# design.net
KiCad netlist of a schematic drawn in EasyEDA Pro
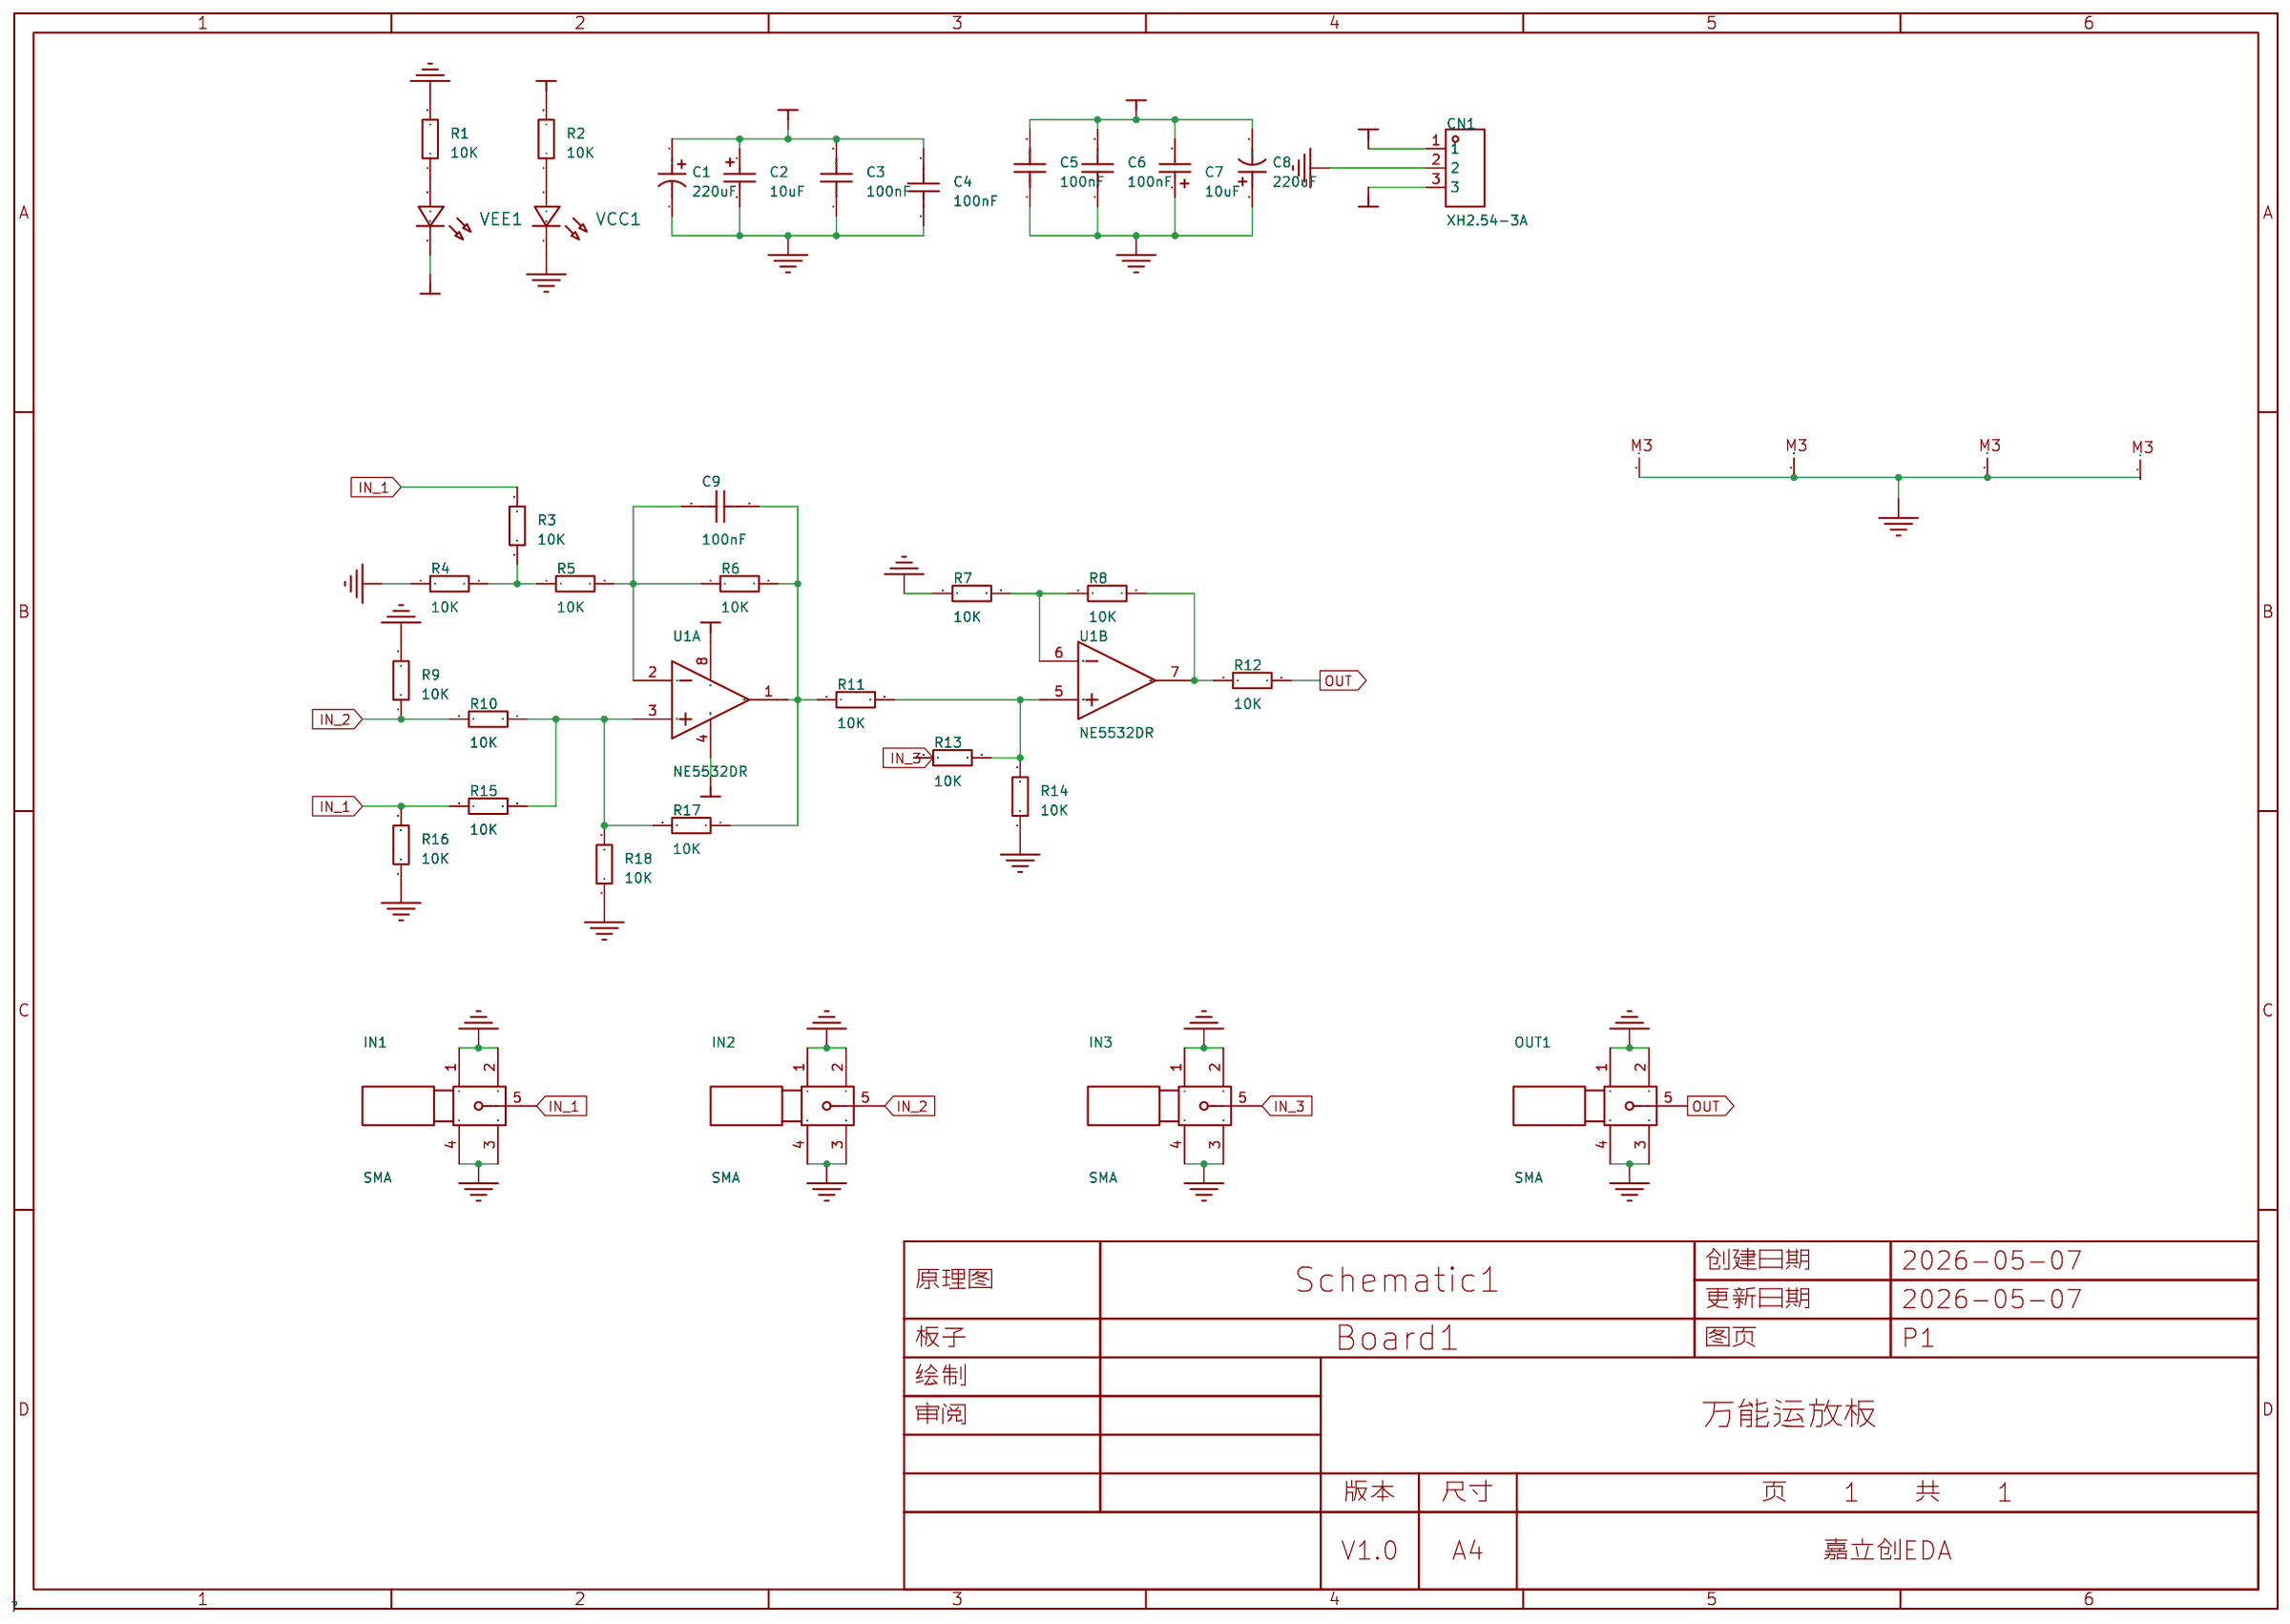
[diagram p0: schematic sheet]

(export (version "E")
  (design (tool "Eeschema 10.0.6"))
  (components
    (comp (ref "C1")
      (value "220uF")
      (footprint "easyedapro:CAP-SMD_BD6.3-L6.6-W6.6-LS7.3-FD-H7.7")
      (fields (field (name "Manufacturer Part") "JVJ25V220M6x8") (field (name "Manufacturer") "JIERR(捷而瑞)"))
      (libsource (lib "easyedapro") (part "JVJ25V220M6X8"))
    )
    (comp (ref "C2")
      (value "10uF")
      (footprint "easyedapro:CAP-SMD_L3.2-W1.6-RD-C7171")
      (fields (field (name "Manufacturer Part") "TAJA106K016RNJ") (field (name "Manufacturer") "Kyocera AVX"))
      (libsource (lib "easyedapro") (part "TAJA106K016RNJ"))
    )
    (comp (ref "C3")
      (value "100nF")
      (footprint "easyedapro:C0603")
      (libsource (lib "easyedapro") (part "Capacitance"))
    )
    (comp (ref "C4")
      (value "100nF")
      (footprint "easyedapro:C0603")
      (libsource (lib "easyedapro") (part "Capacitance"))
    )
    (comp (ref "C5")
      (value "100nF")
      (footprint "easyedapro:C0603")
      (libsource (lib "easyedapro") (part "Capacitance"))
    )
    (comp (ref "C6")
      (value "100nF")
      (footprint "easyedapro:C0603")
      (libsource (lib "easyedapro") (part "Capacitance"))
    )
    (comp (ref "C7")
      (value "10uF")
      (footprint "easyedapro:CAP-SMD_L3.2-W1.6-RD-C7171")
      (fields (field (name "Manufacturer Part") "TAJA106K016RNJ") (field (name "Manufacturer") "Kyocera AVX"))
      (libsource (lib "easyedapro") (part "TAJA106K016RNJ"))
    )
    (comp (ref "C8")
      (value "220uF")
      (footprint "easyedapro:CAP-SMD_BD6.3-L6.6-W6.6-LS7.3-FD-H7.7")
      (fields (field (name "Manufacturer Part") "JVJ25V220M6x8") (field (name "Manufacturer") "JIERR(捷而瑞)"))
      (libsource (lib "easyedapro") (part "JVJ25V220M6X8"))
    )
    (comp (ref "C9")
      (value "100nF")
      (footprint "easyedapro:C0603")
      (libsource (lib "easyedapro") (part "Capacitance"))
    )
    (comp (ref "CN1")
      (value "XH2.54-3A")
      (footprint "easyedapro:CONN-TH_3P-P2.50_HCTL_XH-3A-L")
      (libsource (lib "easyedapro") (part "XH2.54-3A"))
    )
    (comp (ref "IN1")
      (value "SMA")
      (footprint "easyedapro:SMA-SMD_BWSMA-KE-P001")
      (libsource (lib "easyedapro") (part "SMA_C9900018296"))
    )
    (comp (ref "IN2")
      (value "SMA")
      (footprint "easyedapro:SMA-SMD_BWSMA-KE-P001")
      (libsource (lib "easyedapro") (part "SMA_C9900018296"))
    )
    (comp (ref "IN3")
      (value "SMA")
      (footprint "easyedapro:SMA-SMD_BWSMA-KE-P001")
      (libsource (lib "easyedapro") (part "SMA_C9900018296"))
    )
    (comp (ref "M1") (value "~") (footprint "easyedapro:M3") (libsource (lib "easyedapro") (part "螺丝孔")))
    (comp (ref "M2") (value "~") (footprint "easyedapro:M3") (libsource (lib "easyedapro") (part "螺丝孔")))
    (comp (ref "M3") (value "~") (footprint "easyedapro:M3") (libsource (lib "easyedapro") (part "螺丝孔")))
    (comp (ref "M4") (value "~") (footprint "easyedapro:M3") (libsource (lib "easyedapro") (part "螺丝孔")))
    (comp (ref "OUT1")
      (value "SMA")
      (footprint "easyedapro:SMA-SMD_BWSMA-KE-P001")
      (libsource (lib "easyedapro") (part "SMA_C9900018296"))
    )
    (comp (ref "R1") (value "10K") (footprint "easyedapro:R0603") (libsource (lib "easyedapro") (part "电阻")))
    (comp (ref "R2") (value "10K") (footprint "easyedapro:R0603") (libsource (lib "easyedapro") (part "电阻")))
    (comp (ref "R3") (value "10K") (footprint "easyedapro:R0603") (libsource (lib "easyedapro") (part "电阻")))
    (comp (ref "R4") (value "10K") (footprint "easyedapro:R0603") (libsource (lib "easyedapro") (part "电阻")))
    (comp (ref "R5") (value "10K") (footprint "easyedapro:R0603") (libsource (lib "easyedapro") (part "电阻")))
    (comp (ref "R6") (value "10K") (footprint "easyedapro:R0603") (libsource (lib "easyedapro") (part "电阻")))
    (comp (ref "R7") (value "10K") (footprint "easyedapro:R0603") (libsource (lib "easyedapro") (part "电阻")))
    (comp (ref "R8") (value "10K") (footprint "easyedapro:R0603") (libsource (lib "easyedapro") (part "电阻")))
    (comp (ref "R9") (value "10K") (footprint "easyedapro:R0603") (libsource (lib "easyedapro") (part "电阻")))
    (comp (ref "R10") (value "10K") (footprint "easyedapro:R0603") (libsource (lib "easyedapro") (part "电阻")))
    (comp (ref "R11") (value "10K") (footprint "easyedapro:R0603") (libsource (lib "easyedapro") (part "电阻")))
    (comp (ref "R12") (value "10K") (footprint "easyedapro:R0603") (libsource (lib "easyedapro") (part "电阻")))
    (comp (ref "R13") (value "10K") (footprint "easyedapro:R0603") (libsource (lib "easyedapro") (part "电阻")))
    (comp (ref "R14") (value "10K") (footprint "easyedapro:R0603") (libsource (lib "easyedapro") (part "电阻")))
    (comp (ref "R15") (value "10K") (footprint "easyedapro:R0603") (libsource (lib "easyedapro") (part "电阻")))
    (comp (ref "R16") (value "10K") (footprint "easyedapro:R0603") (libsource (lib "easyedapro") (part "电阻")))
    (comp (ref "R17") (value "10K") (footprint "easyedapro:R0603") (libsource (lib "easyedapro") (part "电阻")))
    (comp (ref "R18") (value "10K") (footprint "easyedapro:R0603") (libsource (lib "easyedapro") (part "电阻")))
    (comp (ref "U1")
      (value "NE5532DR")
      (footprint "easyedapro:SOIC-8_L4.9-W3.9-P1.27-LS6.0-BL")
      (fields (field (name "Manufacturer") "TI(德州仪器)"))
      (libsource (lib "easyedapro") (part "NE5532DR"))
    )
    (comp (ref "VCC1")
      (value "~")
      (footprint "easyedapro:LED_0603")
      (libsource (lib "easyedapro") (part "LED_R"))
    )
    (comp (ref "VEE1")
      (value "~")
      (footprint "easyedapro:LED_0603")
      (libsource (lib "easyedapro") (part "LED_R"))
    )
  )
  (nets
    (net (code "1") (name "GND") (class "Default")
      (node (ref "C1") (pin "2") (pinfunction "2_2") (pintype "input"))
      (node (ref "C2") (pin "2") (pinfunction "2_2") (pintype "input"))
      (node (ref "C3") (pin "1") (pinfunction "1_1") (pintype "input"))
      (node (ref "C4") (pin "1") (pinfunction "1_1") (pintype "input"))
      (node (ref "C5") (pin "1") (pinfunction "1_1") (pintype "input"))
      (node (ref "C6") (pin "1") (pinfunction "1_1") (pintype "input"))
      (node (ref "C7") (pin "1") (pinfunction "1_1") (pintype "input"))
      (node (ref "C8") (pin "1") (pinfunction "1_1") (pintype "input"))
      (node (ref "CN1") (pin "2") (pinfunction "2_2") (pintype "unspecified"))
      (node (ref "IN1") (pin "1") (pinfunction "1_1") (pintype "unspecified"))
      (node (ref "IN1") (pin "2") (pinfunction "2_2") (pintype "unspecified"))
      (node (ref "IN1") (pin "3") (pinfunction "3_3") (pintype "unspecified"))
      (node (ref "IN1") (pin "4") (pinfunction "4_4") (pintype "unspecified"))
      (node (ref "IN2") (pin "1") (pinfunction "1_1") (pintype "unspecified"))
      (node (ref "IN2") (pin "2") (pinfunction "2_2") (pintype "unspecified"))
      (node (ref "IN2") (pin "3") (pinfunction "3_3") (pintype "unspecified"))
      (node (ref "IN2") (pin "4") (pinfunction "4_4") (pintype "unspecified"))
      (node (ref "IN3") (pin "1") (pinfunction "1_1") (pintype "unspecified"))
      (node (ref "IN3") (pin "2") (pinfunction "2_2") (pintype "unspecified"))
      (node (ref "IN3") (pin "3") (pinfunction "3_3") (pintype "unspecified"))
      (node (ref "IN3") (pin "4") (pinfunction "4_4") (pintype "unspecified"))
      (node (ref "M1") (pin "1") (pinfunction "1_1") (pintype "input"))
      (node (ref "M2") (pin "1") (pinfunction "1_1") (pintype "input"))
      (node (ref "M3") (pin "1") (pinfunction "1_1") (pintype "input"))
      (node (ref "M4") (pin "1") (pinfunction "1_1") (pintype "input"))
      (node (ref "OUT1") (pin "1") (pinfunction "1_1") (pintype "unspecified"))
      (node (ref "OUT1") (pin "2") (pinfunction "2_2") (pintype "unspecified"))
      (node (ref "OUT1") (pin "3") (pinfunction "3_3") (pintype "unspecified"))
      (node (ref "OUT1") (pin "4") (pinfunction "4_4") (pintype "unspecified"))
      (node (ref "R1") (pin "2") (pinfunction "2_2") (pintype "input"))
      (node (ref "R14") (pin "1") (pinfunction "1_1") (pintype "input"))
      (node (ref "R16") (pin "1") (pinfunction "1_1") (pintype "input"))
      (node (ref "R18") (pin "1") (pinfunction "1_1") (pintype "input"))
      (node (ref "R4") (pin "1") (pinfunction "1_1") (pintype "input"))
      (node (ref "R7") (pin "1") (pinfunction "1_1") (pintype "input"))
      (node (ref "R9") (pin "2") (pinfunction "2_2") (pintype "input"))
      (node (ref "VCC1") (pin "1") (pinfunction "C_1") (pintype "input"))
    )
    (net (code "2") (name "IN_1") (class "Default")
      (node (ref "IN1") (pin "5") (pinfunction "5_5") (pintype "unspecified"))
      (node (ref "R15") (pin "1") (pinfunction "1_1") (pintype "input"))
      (node (ref "R16") (pin "2") (pinfunction "2_2") (pintype "input"))
      (node (ref "R3") (pin "2") (pinfunction "2_2") (pintype "input"))
    )
    (net (code "3") (name "IN_2") (class "Default")
      (node (ref "IN2") (pin "5") (pinfunction "5_5") (pintype "unspecified"))
      (node (ref "R10") (pin "2") (pinfunction "2_2") (pintype "input"))
      (node (ref "R9") (pin "1") (pinfunction "1_1") (pintype "input"))
    )
    (net (code "4") (name "IN_3") (class "Default")
      (node (ref "IN3") (pin "5") (pinfunction "5_5") (pintype "unspecified"))
      (node (ref "R13") (pin "1") (pinfunction "1_1") (pintype "input"))
    )
    (net (code "5") (name "Net-(R3-Pad1)") (class "Default")
      (node (ref "R3") (pin "1") (pinfunction "1_1") (pintype "input"))
      (node (ref "R4") (pin "2") (pinfunction "2_2") (pintype "input"))
      (node (ref "R5") (pin "1") (pinfunction "1_1") (pintype "input"))
    )
    (net (code "6") (name "Net-(U1A-IN1+)") (class "Default")
      (node (ref "R10") (pin "1") (pinfunction "1_1") (pintype "input"))
      (node (ref "R15") (pin "2") (pinfunction "2_2") (pintype "input"))
      (node (ref "R17") (pin "2") (pinfunction "2_2") (pintype "input"))
      (node (ref "R18") (pin "2") (pinfunction "2_2") (pintype "input"))
      (node (ref "U1") (pin "3") (pinfunction "IN1+_3") (pintype "unspecified"))
    )
    (net (code "7") (name "Net-(U1A-IN1-)") (class "Default")
      (node (ref "C9") (pin "1") (pinfunction "1_1") (pintype "input"))
      (node (ref "R5") (pin "2") (pinfunction "2_2") (pintype "input"))
      (node (ref "R6") (pin "1") (pinfunction "1_1") (pintype "input"))
      (node (ref "U1") (pin "2") (pinfunction "IN1-_2") (pintype "unspecified"))
    )
    (net (code "8") (name "Net-(U1A-OUT1)") (class "Default")
      (node (ref "C9") (pin "2") (pinfunction "2_2") (pintype "input"))
      (node (ref "R11") (pin "1") (pinfunction "1_1") (pintype "input"))
      (node (ref "R17") (pin "1") (pinfunction "1_1") (pintype "input"))
      (node (ref "R6") (pin "2") (pinfunction "2_2") (pintype "input"))
      (node (ref "U1") (pin "1") (pinfunction "OUT1_1") (pintype "output"))
    )
    (net (code "9") (name "Net-(U1B-IN2+)") (class "Default")
      (node (ref "R11") (pin "2") (pinfunction "2_2") (pintype "input"))
      (node (ref "R13") (pin "2") (pinfunction "2_2") (pintype "input"))
      (node (ref "R14") (pin "2") (pinfunction "2_2") (pintype "input"))
      (node (ref "U1") (pin "5") (pinfunction "IN2+_5") (pintype "unspecified"))
    )
    (net (code "10") (name "Net-(U1B-IN2-)") (class "Default")
      (node (ref "R7") (pin "2") (pinfunction "2_2") (pintype "input"))
      (node (ref "R8") (pin "1") (pinfunction "1_1") (pintype "input"))
      (node (ref "U1") (pin "6") (pinfunction "IN2-_6") (pintype "unspecified"))
    )
    (net (code "11") (name "Net-(U1B-OUT2)") (class "Default")
      (node (ref "R12") (pin "1") (pinfunction "1_1") (pintype "input"))
      (node (ref "R8") (pin "2") (pinfunction "2_2") (pintype "input"))
      (node (ref "U1") (pin "7") (pinfunction "OUT2_7") (pintype "output"))
    )
    (net (code "12") (name "Net-(VCC1-A)") (class "Default")
      (node (ref "R2") (pin "1") (pinfunction "1_1") (pintype "input"))
      (node (ref "VCC1") (pin "2") (pinfunction "A_2") (pintype "input"))
    )
    (net (code "13") (name "Net-(VEE1-A)") (class "Default")
      (node (ref "R1") (pin "1") (pinfunction "1_1") (pintype "input"))
      (node (ref "VEE1") (pin "2") (pinfunction "A_2") (pintype "input"))
    )
    (net (code "14") (name "OUT") (class "Default")
      (node (ref "OUT1") (pin "5") (pinfunction "5_5") (pintype "unspecified"))
      (node (ref "R12") (pin "2") (pinfunction "2_2") (pintype "input"))
    )
    (net (code "15") (name "VCC") (class "Default")
      (node (ref "C1") (pin "1") (pinfunction "1_1") (pintype "input"))
      (node (ref "C2") (pin "1") (pinfunction "1_1") (pintype "input"))
      (node (ref "C3") (pin "2") (pinfunction "2_2") (pintype "input"))
      (node (ref "C4") (pin "2") (pinfunction "2_2") (pintype "input"))
      (node (ref "CN1") (pin "1") (pinfunction "1_1") (pintype "unspecified"))
      (node (ref "R2") (pin "2") (pinfunction "2_2") (pintype "input"))
      (node (ref "U1") (pin "8") (pinfunction "VCC+_8") (pintype "unspecified"))
    )
    (net (code "16") (name "VEE") (class "Default")
      (node (ref "C5") (pin "2") (pinfunction "2_2") (pintype "input"))
      (node (ref "C6") (pin "2") (pinfunction "2_2") (pintype "input"))
      (node (ref "C7") (pin "2") (pinfunction "2_2") (pintype "input"))
      (node (ref "C8") (pin "2") (pinfunction "2_2") (pintype "input"))
      (node (ref "CN1") (pin "3") (pinfunction "3_3") (pintype "unspecified"))
      (node (ref "U1") (pin "4") (pinfunction "VCC-/GND_4") (pintype "unspecified"))
      (node (ref "VEE1") (pin "1") (pinfunction "C_1") (pintype "input"))
    )
  )
)
